# UCC28070_Control.net
KiCad netlist of a schematic drawn in Altium Designer
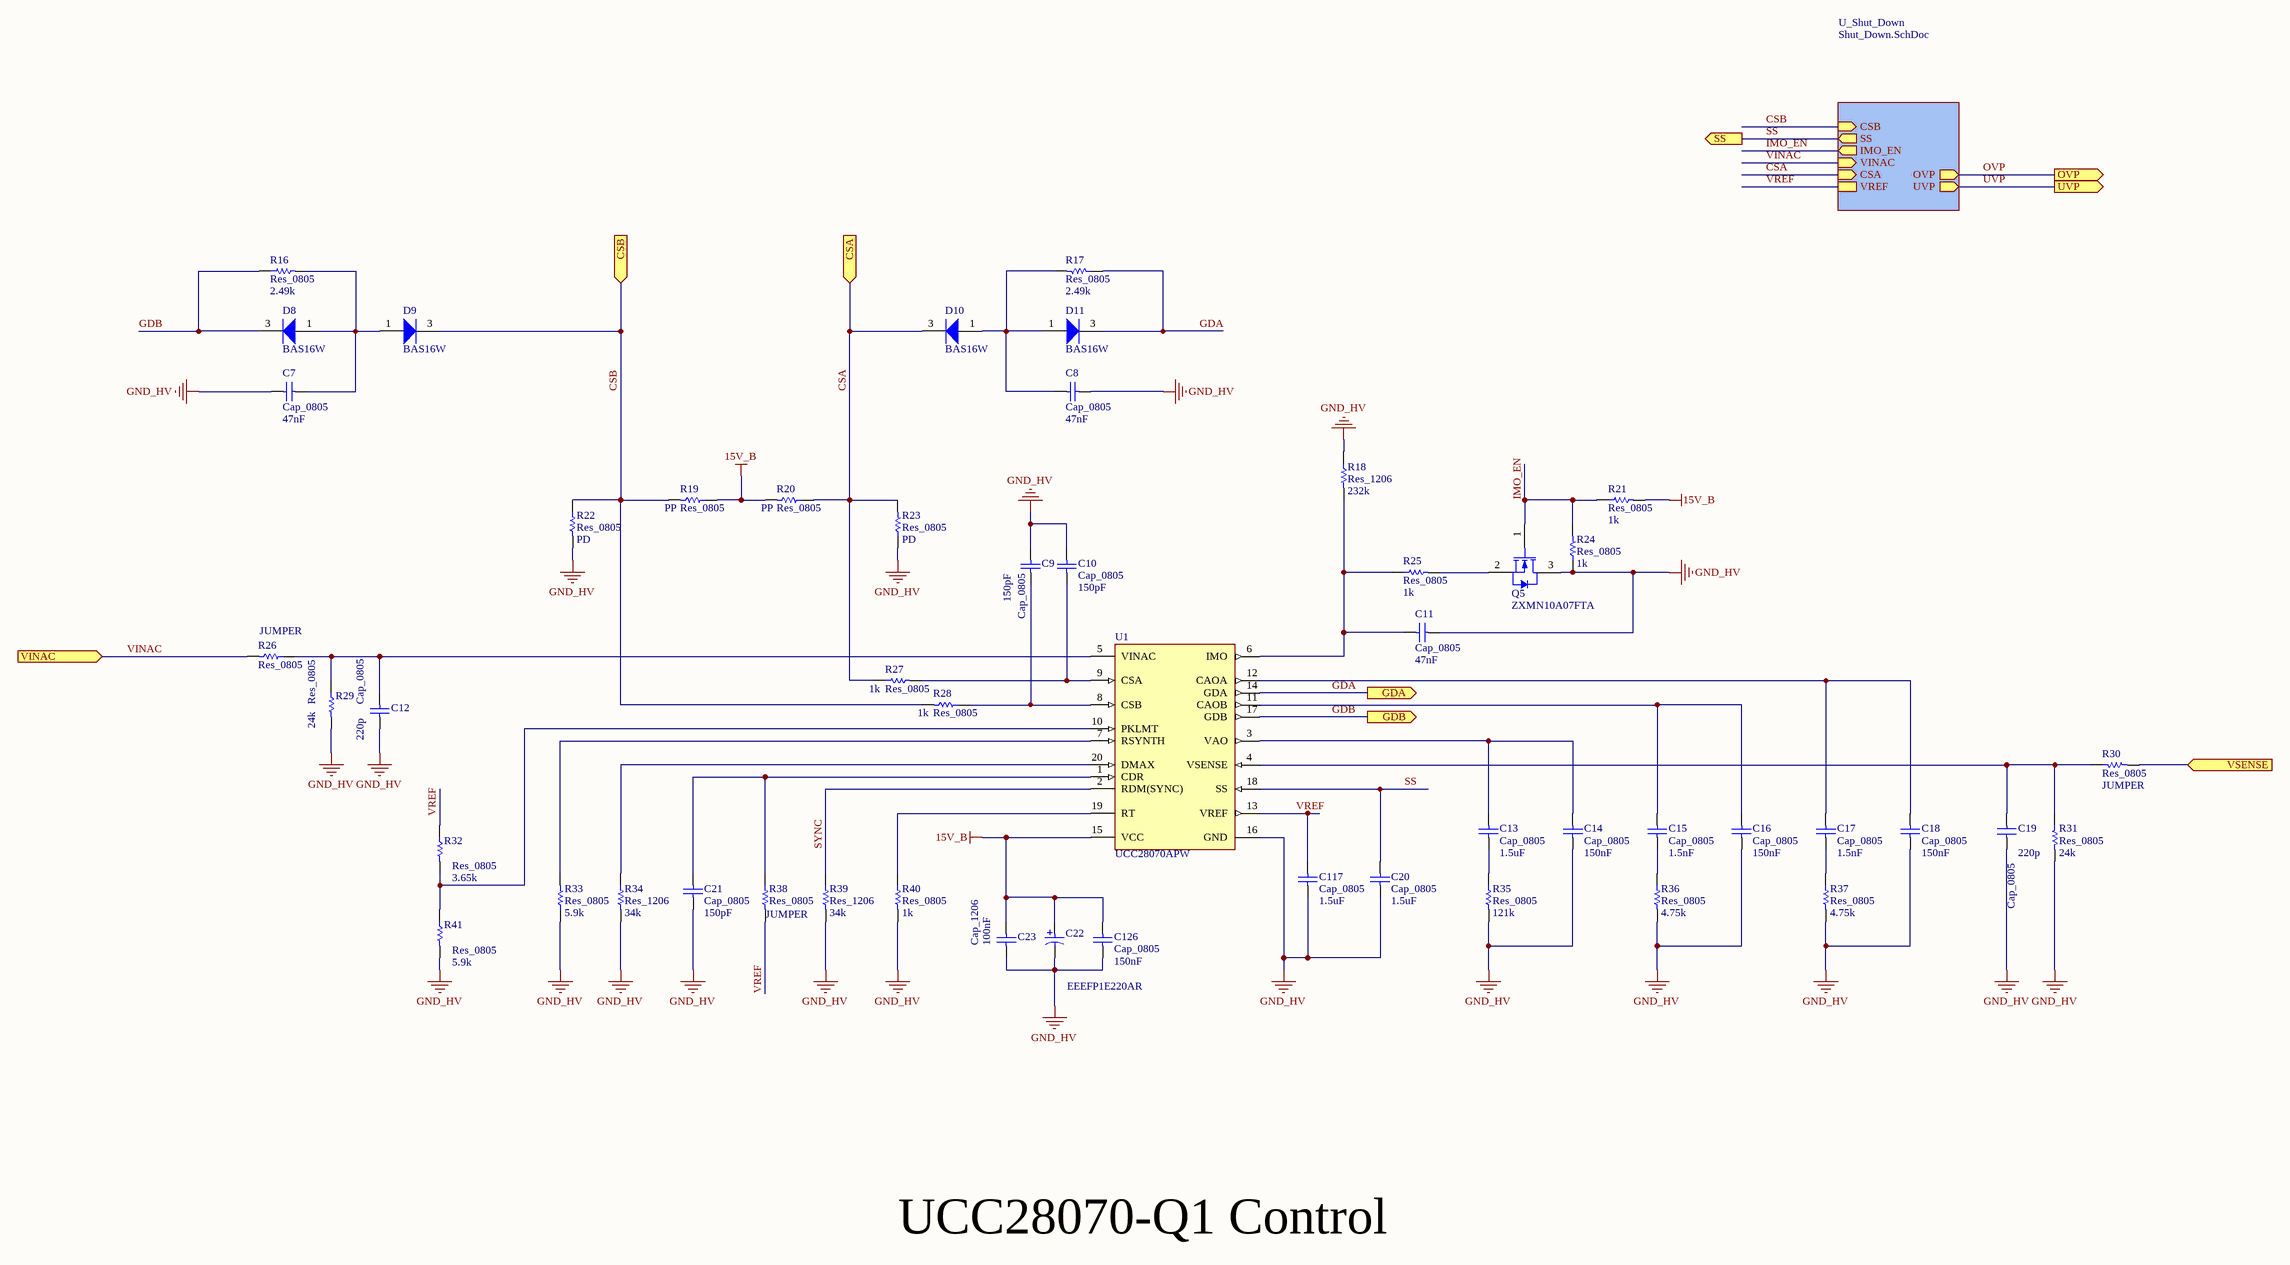
[diagram p0: UCC28070_Control.SchDoc]

(export (version "E")
  (design (tool "Eeschema 10.0.6"))
  (components
    (comp (ref "C7")
      (value "Cap_0805")
      (footprint "SMD-0805C")
      (description "Capacitor")
      (fields (field (name "SIZE") "47nF") (field (name "PUBLISHER") "Altium Limited"))
      (libsource (lib "Miscellaneous Devices") (part "Cap"))
    )
    (comp (ref "C8")
      (value "Cap_0805")
      (footprint "SMD-0805C")
      (description "Capacitor")
      (fields (field (name "SIZE") "47nF") (field (name "PUBLISHER") "Altium Limited"))
      (libsource (lib "Miscellaneous Devices") (part "Cap"))
    )
    (comp (ref "C9")
      (value "Cap_0805")
      (footprint "SMD-0805C")
      (description "Capacitor")
      (fields (field (name "SIZE") "150pF") (field (name "PUBLISHER") "Altium Limited"))
      (libsource (lib "Miscellaneous Devices") (part "Cap"))
    )
    (comp (ref "C10")
      (value "Cap_0805")
      (footprint "SMD-0805C")
      (description "Capacitor")
      (fields (field (name "SIZE") "150pF") (field (name "PUBLISHER") "Altium Limited"))
      (libsource (lib "Miscellaneous Devices") (part "Cap"))
    )
    (comp (ref "C11")
      (value "Cap_0805")
      (footprint "SMD-0805C")
      (description "Capacitor")
      (fields (field (name "SIZE") "47nF") (field (name "PUBLISHER") "Altium Limited"))
      (libsource (lib "Miscellaneous Devices") (part "Cap"))
    )
    (comp (ref "C12")
      (value "Cap_0805")
      (footprint "SMD-0805C")
      (description "Capacitor")
      (fields (field (name "SIZE") "220p") (field (name "PUBLISHER") "Altium Limited"))
      (libsource (lib "Miscellaneous Devices") (part "Cap"))
    )
    (comp (ref "C13")
      (value "Cap_0805")
      (footprint "SMD-0805C")
      (description "Capacitor")
      (fields (field (name "SIZE") "1.5uF") (field (name "PUBLISHER") "Altium Limited"))
      (libsource (lib "Miscellaneous Devices") (part "Cap"))
    )
    (comp (ref "C14")
      (value "Cap_0805")
      (footprint "SMD-0805C")
      (description "Capacitor")
      (fields (field (name "SIZE") "150nF") (field (name "PUBLISHER") "Altium Limited"))
      (libsource (lib "Miscellaneous Devices") (part "Cap"))
    )
    (comp (ref "C15")
      (value "Cap_0805")
      (footprint "SMD-0805C")
      (description "Capacitor")
      (fields (field (name "SIZE") "1.5nF") (field (name "PUBLISHER") "Altium Limited"))
      (libsource (lib "Miscellaneous Devices") (part "Cap"))
    )
    (comp (ref "C16")
      (value "Cap_0805")
      (footprint "SMD-0805C")
      (description "Capacitor")
      (fields (field (name "SIZE") "150nF") (field (name "PUBLISHER") "Altium Limited"))
      (libsource (lib "Miscellaneous Devices") (part "Cap"))
    )
    (comp (ref "C17")
      (value "Cap_0805")
      (footprint "SMD-0805C")
      (description "Capacitor")
      (fields (field (name "SIZE") "1.5nF") (field (name "PUBLISHER") "Altium Limited"))
      (libsource (lib "Miscellaneous Devices") (part "Cap"))
    )
    (comp (ref "C18")
      (value "Cap_0805")
      (footprint "SMD-0805C")
      (description "Capacitor")
      (fields (field (name "SIZE") "150nF") (field (name "PUBLISHER") "Altium Limited"))
      (libsource (lib "Miscellaneous Devices") (part "Cap"))
    )
    (comp (ref "C19")
      (value "Cap_0805")
      (footprint "SMD-0805C")
      (description "Capacitor")
      (fields (field (name "SIZE") "220p") (field (name "PUBLISHER") "Altium Limited"))
      (libsource (lib "Miscellaneous Devices") (part "Cap"))
    )
    (comp (ref "C20")
      (value "Cap_0805")
      (footprint "SMD-0805C")
      (description "Capacitor")
      (fields (field (name "SIZE") "1.5uF") (field (name "PUBLISHER") "Altium Limited"))
      (libsource (lib "Miscellaneous Devices") (part "Cap"))
    )
    (comp (ref "C21")
      (value "Cap_0805")
      (footprint "SMD-0805C")
      (description "Capacitor")
      (fields (field (name "SIZE") "150pF") (field (name "PUBLISHER") "Altium Limited"))
      (libsource (lib "Miscellaneous Devices") (part "Cap"))
    )
    (comp (ref "C22")
      (value "EEEFP1E220AR")
      (footprint "PNSC-FP-V-C_V")
      (fields (field (name "MANUFACTURER") "Panasonic"))
      (libsource (lib "Altium Content Vault") (part "CAP-P-2"))
    )
    (comp (ref "C23")
      (value "Cap_1206")
      (footprint "SMD-1206C")
      (description "Capacitor")
      (fields (field (name "ALTIUM_VALUE") "100nF") (field (name "PUBLISHER") "Altium Limited"))
      (libsource (lib "Miscellaneous Devices") (part "Cap"))
    )
    (comp (ref "C117")
      (value "Cap_0805")
      (footprint "SMD-0805C")
      (description "Capacitor")
      (fields (field (name "SIZE") "1.5uF") (field (name "PUBLISHER") "Altium Limited"))
      (libsource (lib "Miscellaneous Devices") (part "Cap"))
    )
    (comp (ref "C126")
      (value "Cap_0805")
      (footprint "SMD-0805C")
      (description "Capacitor")
      (fields (field (name "SIZE") "150nF") (field (name "PUBLISHER") "Altium Limited"))
      (libsource (lib "Miscellaneous Devices") (part "Cap"))
    )
    (comp (ref "D8")
      (value "BAS16W")
      (footprint "SOT95P278X110-3N")
      (description "Silicon Switching Diode, SOT323, Reel, Green")
      (fields (field (name "MANUFACTURER") "Infineon"))
      (libsource (lib "PFC_Stage") (part "BAS16"))
    )
    (comp (ref "D9")
      (value "BAS16W")
      (footprint "SOT95P278X110-3N")
      (description "Silicon Switching Diode, SOT323, Reel, Green")
      (fields (field (name "MANUFACTURER") "Infineon"))
      (libsource (lib "PFC_Stage") (part "BAS16"))
    )
    (comp (ref "D10")
      (value "BAS16W")
      (footprint "SOT95P278X110-3N")
      (description "Silicon Switching Diode, SOT323, Reel, Green")
      (fields (field (name "MANUFACTURER") "Infineon"))
      (libsource (lib "PFC_Stage") (part "BAS16"))
    )
    (comp (ref "D11")
      (value "BAS16W")
      (footprint "SOT95P278X110-3N")
      (description "Silicon Switching Diode, SOT323, Reel, Green")
      (fields (field (name "MANUFACTURER") "Infineon"))
      (libsource (lib "PFC_Stage") (part "BAS16"))
    )
    (comp (ref "Q5")
      (value "ZXMN10A07FTA")
      (footprint "DIOD-SOT23-3_D_V")
      (description "N-Channel Enhancement Mode MOSFET, 100 V, -55 to 150 degC, 3-Pin SOT23, RoHS, Tape and Reel")
      (fields (field (name "MANUFACTURER") "Diodes Inc"))
      (libsource (lib "Altium Content Vault") (part "NEMOS-GSD-3"))
    )
    (comp (ref "R16")
      (value "Res_0805")
      (footprint "WRIS-KSKE_0805_H=0.6mm")
      (description "Resistor")
      (fields (field (name "ALTIUM_VALUE") "2.49k") (field (name "PUBLISHER") "Altium Limited"))
      (libsource (lib "Miscellaneous Devices") (part "Res1"))
    )
    (comp (ref "R17")
      (value "Res_0805")
      (footprint "WRIS-KSKE_0805_H=0.6mm")
      (description "Resistor")
      (fields (field (name "ALTIUM_VALUE") "2.49k") (field (name "PUBLISHER") "Altium Limited"))
      (libsource (lib "Miscellaneous Devices") (part "Res1"))
    )
    (comp (ref "R18")
      (value "Res_1206")
      (footprint "WRIS-KSKE_1206_H=0.6mm")
      (description "Resistor")
      (fields (field (name "ALTIUM_VALUE") "232k") (field (name "PUBLISHER") "Altium Limited"))
      (libsource (lib "Miscellaneous Devices") (part "Res1"))
    )
    (comp (ref "R19")
      (value "Res_0805")
      (footprint "WRIS-KSKE_0805_H=0.6mm")
      (description "Resistor")
      (fields (field (name "ALTIUM_VALUE") "PP") (field (name "PUBLISHER") "Altium Limited"))
      (libsource (lib "Miscellaneous Devices") (part "Res1"))
    )
    (comp (ref "R20")
      (value "Res_0805")
      (footprint "WRIS-KSKE_0805_H=0.6mm")
      (description "Resistor")
      (fields (field (name "ALTIUM_VALUE") "PP") (field (name "PUBLISHER") "Altium Limited"))
      (libsource (lib "Miscellaneous Devices") (part "Res1"))
    )
    (comp (ref "R21")
      (value "Res_0805")
      (footprint "WRIS-KSKE_0805_H=0.6mm")
      (description "Resistor")
      (fields (field (name "ALTIUM_VALUE") "1k") (field (name "PUBLISHER") "Altium Limited"))
      (libsource (lib "Miscellaneous Devices") (part "Res1"))
    )
    (comp (ref "R22")
      (value "Res_0805")
      (footprint "WRIS-KSKE_0805_H=0.6mm")
      (description "Resistor")
      (fields (field (name "ALTIUM_VALUE") "PD") (field (name "PUBLISHER") "Altium Limited"))
      (libsource (lib "Miscellaneous Devices") (part "Res1"))
    )
    (comp (ref "R23")
      (value "Res_0805")
      (footprint "WRIS-KSKE_0805_H=0.6mm")
      (description "Resistor")
      (fields (field (name "ALTIUM_VALUE") "PD") (field (name "PUBLISHER") "Altium Limited"))
      (libsource (lib "Miscellaneous Devices") (part "Res1"))
    )
    (comp (ref "R24")
      (value "Res_0805")
      (footprint "WRIS-KSKE_0805_H=0.6mm")
      (description "Resistor")
      (fields (field (name "ALTIUM_VALUE") "1k") (field (name "PUBLISHER") "Altium Limited"))
      (libsource (lib "Miscellaneous Devices") (part "Res1"))
    )
    (comp (ref "R25")
      (value "Res_0805")
      (footprint "WRIS-KSKE_0805_H=0.6mm")
      (description "Resistor")
      (fields (field (name "ALTIUM_VALUE") "1k") (field (name "PUBLISHER") "Altium Limited"))
      (libsource (lib "Miscellaneous Devices") (part "Res1"))
    )
    (comp (ref "R26")
      (value "Res_0805")
      (footprint "WRIS-KSKE_0805_H=0.6mm")
      (description "Resistor")
      (fields (field (name "ALTIUM_VALUE") "JUMPER") (field (name "PUBLISHER") "Altium Limited"))
      (libsource (lib "Miscellaneous Devices") (part "Res1"))
    )
    (comp (ref "R27")
      (value "Res_0805")
      (footprint "WRIS-KSKE_0805_H=0.6mm")
      (description "Resistor")
      (fields (field (name "ALTIUM_VALUE") "1k") (field (name "PUBLISHER") "Altium Limited"))
      (libsource (lib "Miscellaneous Devices") (part "Res1"))
    )
    (comp (ref "R28")
      (value "Res_0805")
      (footprint "WRIS-KSKE_0805_H=0.6mm")
      (description "Resistor")
      (fields (field (name "ALTIUM_VALUE") "1k") (field (name "PUBLISHER") "Altium Limited"))
      (libsource (lib "Miscellaneous Devices") (part "Res1"))
    )
    (comp (ref "R29")
      (value "Res_0805")
      (footprint "WRIS-KSKE_0805_H=0.6mm")
      (description "Resistor")
      (fields (field (name "ALTIUM_VALUE") "24k") (field (name "PUBLISHER") "Altium Limited"))
      (libsource (lib "Miscellaneous Devices") (part "Res1"))
    )
    (comp (ref "R30")
      (value "Res_0805")
      (footprint "WRIS-KSKE_0805_H=0.6mm")
      (description "Resistor")
      (fields (field (name "ALTIUM_VALUE") "JUMPER") (field (name "PUBLISHER") "Altium Limited"))
      (libsource (lib "Miscellaneous Devices") (part "Res1"))
    )
    (comp (ref "R31")
      (value "Res_0805")
      (footprint "WRIS-KSKE_0805_H=0.6mm")
      (description "Resistor")
      (fields (field (name "ALTIUM_VALUE") "24k") (field (name "PUBLISHER") "Altium Limited"))
      (libsource (lib "Miscellaneous Devices") (part "Res1"))
    )
    (comp (ref "R32")
      (value "Res_0805")
      (footprint "WRIS-KSKE_0805_H=0.6mm")
      (description "Resistor")
      (fields (field (name "ALTIUM_VALUE") "3.65k") (field (name "PUBLISHER") "Altium Limited"))
      (libsource (lib "Miscellaneous Devices") (part "Res1"))
    )
    (comp (ref "R33")
      (value "Res_0805")
      (footprint "WRIS-KSKE_0805_H=0.6mm")
      (description "Resistor")
      (fields (field (name "ALTIUM_VALUE") "5.9k") (field (name "PUBLISHER") "Altium Limited"))
      (libsource (lib "Miscellaneous Devices") (part "Res1"))
    )
    (comp (ref "R34")
      (value "Res_1206")
      (footprint "WRIS-KSKE_1206_H=0.6mm")
      (description "Resistor")
      (fields (field (name "ALTIUM_VALUE") "34k") (field (name "PUBLISHER") "Altium Limited"))
      (libsource (lib "Miscellaneous Devices") (part "Res1"))
    )
    (comp (ref "R35")
      (value "Res_0805")
      (footprint "WRIS-KSKE_0805_H=0.6mm")
      (description "Resistor")
      (fields (field (name "ALTIUM_VALUE") "121k") (field (name "PUBLISHER") "Altium Limited"))
      (libsource (lib "Miscellaneous Devices") (part "Res1"))
    )
    (comp (ref "R36")
      (value "Res_0805")
      (footprint "WRIS-KSKE_0805_H=0.6mm")
      (description "Resistor")
      (fields (field (name "ALTIUM_VALUE") "4.75k") (field (name "PUBLISHER") "Altium Limited"))
      (libsource (lib "Miscellaneous Devices") (part "Res1"))
    )
    (comp (ref "R37")
      (value "Res_0805")
      (footprint "WRIS-KSKE_0805_H=0.6mm")
      (description "Resistor")
      (fields (field (name "ALTIUM_VALUE") "4.75k") (field (name "PUBLISHER") "Altium Limited"))
      (libsource (lib "Miscellaneous Devices") (part "Res1"))
    )
    (comp (ref "R38")
      (value "Res_0805")
      (footprint "WRIS-KSKE_0805_H=0.6mm")
      (description "Resistor")
      (fields (field (name "ALTIUM_VALUE") "JUMPER") (field (name "PUBLISHER") "Altium Limited"))
      (libsource (lib "Miscellaneous Devices") (part "Res1"))
    )
    (comp (ref "R39")
      (value "Res_1206")
      (footprint "WRIS-KSKE_1206_H=0.6mm")
      (description "Resistor")
      (fields (field (name "ALTIUM_VALUE") "34k") (field (name "PUBLISHER") "Altium Limited"))
      (libsource (lib "Miscellaneous Devices") (part "Res1"))
    )
    (comp (ref "R40")
      (value "Res_0805")
      (footprint "WRIS-KSKE_0805_H=0.6mm")
      (description "Resistor")
      (fields (field (name "ALTIUM_VALUE") "1k") (field (name "PUBLISHER") "Altium Limited"))
      (libsource (lib "Miscellaneous Devices") (part "Res1"))
    )
    (comp (ref "R41")
      (value "Res_0805")
      (footprint "WRIS-KSKE_0805_H=0.6mm")
      (description "Resistor")
      (fields (field (name "ALTIUM_VALUE") "5.9k") (field (name "PUBLISHER") "Altium Limited"))
      (libsource (lib "Miscellaneous Devices") (part "Res1"))
    )
    (comp (ref "U1")
      (value "UCC28070APW")
      (footprint "TSOP65P640X120_HS-21N")
      (fields (field (name "MANUFACTURER") "Texas Instruments"))
      (libsource (lib "PFC_Stage") (part "CMP-0333-00336-2"))
    )
  )
  (nets
    (net (code "1") (name "/CSA") (class "Default")
      (node (ref "D10") (pin "3") (pinfunction "K_3") (pintype "passive"))
      (node (ref "R20") (pin "1") (pinfunction "1_1") (pintype "passive"))
      (node (ref "R23") (pin "2") (pinfunction "2_2") (pintype "passive"))
      (node (ref "R27") (pin "1") (pinfunction "1_1") (pintype "passive"))
    )
    (net (code "2") (name "/CSB") (class "Default")
      (node (ref "D9") (pin "3") (pinfunction "K_3") (pintype "passive"))
      (node (ref "R19") (pin "2") (pinfunction "2_2") (pintype "passive"))
      (node (ref "R22") (pin "1") (pinfunction "1_1") (pintype "passive"))
      (node (ref "R28") (pin "2") (pinfunction "2_2") (pintype "passive"))
    )
    (net (code "3") (name "/GDA") (class "Default")
      (node (ref "D11") (pin "3") (pinfunction "K_3") (pintype "passive"))
      (node (ref "R17") (pin "1") (pinfunction "1_1") (pintype "passive"))
      (node (ref "U1") (pin "14") (pinfunction "GDA_14") (pintype "output"))
    )
    (net (code "4") (name "/GDB") (class "Default")
      (node (ref "D8") (pin "3") (pinfunction "K_3") (pintype "passive"))
      (node (ref "R16") (pin "1") (pinfunction "1_1") (pintype "passive"))
      (node (ref "U1") (pin "17") (pinfunction "GDB_17") (pintype "output"))
    )
    (net (code "5") (name "/IMO_EN") (class "Default")
      (node (ref "Q5") (pin "1") (pinfunction "G_1") (pintype "passive"))
      (node (ref "R21") (pin "1") (pinfunction "1_1") (pintype "passive"))
      (node (ref "R24") (pin "2") (pinfunction "2_2") (pintype "passive"))
    )
    (net (code "7") (name "/SS") (class "Default")
      (node (ref "C20") (pin "1") (pinfunction "1_1") (pintype "passive"))
      (node (ref "U1") (pin "18") (pinfunction "SS_18") (pintype "input"))
    )
    (net (code "8") (name "/SYNC") (class "Default")
      (node (ref "R39") (pin "1") (pinfunction "1_1") (pintype "passive"))
      (node (ref "U1") (pin "2") (pinfunction "RDM(SYNC)_2") (pintype "passive"))
    )
    (net (code "10") (name "/VINAC") (class "Default")
      (node (ref "R26") (pin "2") (pinfunction "2_2") (pintype "passive"))
    )
    (net (code "11") (name "/VREF") (class "Default")
      (node (ref "C117") (pin "1") (pinfunction "1_1") (pintype "passive"))
      (node (ref "R32") (pin "1") (pinfunction "1_1") (pintype "passive"))
      (node (ref "R38") (pin "2") (pinfunction "2_2") (pintype "passive"))
      (node (ref "U1") (pin "13") (pinfunction "VREF_13") (pintype "output"))
    )
    (net (code "12") (name "/VSENSE") (class "Default")
      (node (ref "R30") (pin "2") (pinfunction "2_2") (pintype "passive"))
    )
    (net (code "13") (name "15V_B") (class "Default")
      (node (ref "C126") (pin "1") (pinfunction "1_1") (pintype "passive"))
      (node (ref "C22") (pin "1") (pinfunction "1_1") (pintype "passive"))
      (node (ref "C23") (pin "1") (pinfunction "1_1") (pintype "passive"))
      (node (ref "R19") (pin "1") (pinfunction "1_1") (pintype "passive"))
      (node (ref "R20") (pin "2") (pinfunction "2_2") (pintype "passive"))
      (node (ref "R21") (pin "2") (pinfunction "2_2") (pintype "passive"))
      (node (ref "U1") (pin "15") (pinfunction "VCC_15") (pintype "power_in"))
    )
    (net (code "14") (name "GND_HV") (class "Default")
      (node (ref "C10") (pin "1") (pinfunction "1_1") (pintype "passive"))
      (node (ref "C11") (pin "2") (pinfunction "2_2") (pintype "passive"))
      (node (ref "C117") (pin "2") (pinfunction "2_2") (pintype "passive"))
      (node (ref "C12") (pin "2") (pinfunction "2_2") (pintype "passive"))
      (node (ref "C126") (pin "2") (pinfunction "2_2") (pintype "passive"))
      (node (ref "C14") (pin "2") (pinfunction "2_2") (pintype "passive"))
      (node (ref "C16") (pin "2") (pinfunction "2_2") (pintype "passive"))
      (node (ref "C18") (pin "2") (pinfunction "2_2") (pintype "passive"))
      (node (ref "C19") (pin "2") (pinfunction "2_2") (pintype "passive"))
      (node (ref "C20") (pin "2") (pinfunction "2_2") (pintype "passive"))
      (node (ref "C21") (pin "2") (pinfunction "2_2") (pintype "passive"))
      (node (ref "C22") (pin "2") (pinfunction "2_2") (pintype "passive"))
      (node (ref "C23") (pin "2") (pinfunction "2_2") (pintype "passive"))
      (node (ref "C7") (pin "1") (pinfunction "1_1") (pintype "passive"))
      (node (ref "C8") (pin "1") (pinfunction "1_1") (pintype "passive"))
      (node (ref "C9") (pin "1") (pinfunction "1_1") (pintype "passive"))
      (node (ref "Q5") (pin "3") (pinfunction "D_3") (pintype "passive"))
      (node (ref "R18") (pin "1") (pinfunction "1_1") (pintype "passive"))
      (node (ref "R22") (pin "2") (pinfunction "2_2") (pintype "passive"))
      (node (ref "R23") (pin "1") (pinfunction "1_1") (pintype "passive"))
      (node (ref "R24") (pin "1") (pinfunction "1_1") (pintype "passive"))
      (node (ref "R29") (pin "2") (pinfunction "2_2") (pintype "passive"))
      (node (ref "R31") (pin "2") (pinfunction "2_2") (pintype "passive"))
      (node (ref "R33") (pin "1") (pinfunction "1_1") (pintype "passive"))
      (node (ref "R34") (pin "2") (pinfunction "2_2") (pintype "passive"))
      (node (ref "R35") (pin "2") (pinfunction "2_2") (pintype "passive"))
      (node (ref "R36") (pin "2") (pinfunction "2_2") (pintype "passive"))
      (node (ref "R37") (pin "2") (pinfunction "2_2") (pintype "passive"))
      (node (ref "R39") (pin "2") (pinfunction "2_2") (pintype "passive"))
      (node (ref "R40") (pin "2") (pinfunction "2_2") (pintype "passive"))
      (node (ref "R41") (pin "2") (pinfunction "2_2") (pintype "passive"))
      (node (ref "U1") (pin "16") (pinfunction "GND_16") (pintype "power_in"))
    )
    (net (code "15") (name "Net-(C13-Pad2)") (class "Default")
      (node (ref "C13") (pin "2") (pinfunction "2_2") (pintype "passive"))
      (node (ref "R35") (pin "1") (pinfunction "1_1") (pintype "passive"))
    )
    (net (code "16") (name "Net-(C15-Pad2)") (class "Default")
      (node (ref "C15") (pin "2") (pinfunction "2_2") (pintype "passive"))
      (node (ref "R36") (pin "1") (pinfunction "1_1") (pintype "passive"))
    )
    (net (code "17") (name "Net-(C17-Pad2)") (class "Default")
      (node (ref "C17") (pin "2") (pinfunction "2_2") (pintype "passive"))
      (node (ref "R37") (pin "1") (pinfunction "1_1") (pintype "passive"))
    )
    (net (code "18") (name "Net-(D8-A)") (class "Default")
      (node (ref "C7") (pin "2") (pinfunction "2_2") (pintype "passive"))
      (node (ref "D8") (pin "1") (pinfunction "A_1") (pintype "passive"))
      (node (ref "D9") (pin "1") (pinfunction "A_1") (pintype "passive"))
      (node (ref "R16") (pin "2") (pinfunction "2_2") (pintype "passive"))
    )
    (net (code "19") (name "Net-(D10-A)") (class "Default")
      (node (ref "C8") (pin "2") (pinfunction "2_2") (pintype "passive"))
      (node (ref "D10") (pin "1") (pinfunction "A_1") (pintype "passive"))
      (node (ref "D11") (pin "1") (pinfunction "A_1") (pintype "passive"))
      (node (ref "R17") (pin "2") (pinfunction "2_2") (pintype "passive"))
    )
    (net (code "20") (name "Net-(Q5-S)") (class "Default")
      (node (ref "Q5") (pin "2") (pinfunction "S_2") (pintype "passive"))
      (node (ref "R25") (pin "2") (pinfunction "2_2") (pintype "passive"))
    )
    (net (code "21") (name "Net-(U1-CAOA)") (class "Default")
      (node (ref "C17") (pin "1") (pinfunction "1_1") (pintype "passive"))
      (node (ref "C18") (pin "1") (pinfunction "1_1") (pintype "passive"))
      (node (ref "U1") (pin "12") (pinfunction "CAOA_12") (pintype "output"))
    )
    (net (code "22") (name "Net-(U1-CAOB)") (class "Default")
      (node (ref "C15") (pin "1") (pinfunction "1_1") (pintype "passive"))
      (node (ref "C16") (pin "1") (pinfunction "1_1") (pintype "passive"))
      (node (ref "U1") (pin "11") (pinfunction "CAOB_11") (pintype "output"))
    )
    (net (code "23") (name "Net-(U1-CDR)") (class "Default")
      (node (ref "C21") (pin "1") (pinfunction "1_1") (pintype "passive"))
      (node (ref "R38") (pin "1") (pinfunction "1_1") (pintype "passive"))
      (node (ref "U1") (pin "1") (pinfunction "CDR_1") (pintype "input"))
    )
    (net (code "24") (name "Net-(U1-CSA)") (class "Default")
      (node (ref "C10") (pin "2") (pinfunction "2_2") (pintype "passive"))
      (node (ref "R27") (pin "2") (pinfunction "2_2") (pintype "passive"))
      (node (ref "U1") (pin "9") (pinfunction "CSA_9") (pintype "input"))
    )
    (net (code "25") (name "Net-(U1-CSB)") (class "Default")
      (node (ref "C9") (pin "2") (pinfunction "2_2") (pintype "passive"))
      (node (ref "R28") (pin "1") (pinfunction "1_1") (pintype "passive"))
      (node (ref "U1") (pin "8") (pinfunction "CSB_8") (pintype "input"))
    )
    (net (code "26") (name "Net-(U1-DMAX)") (class "Default")
      (node (ref "R34") (pin "1") (pinfunction "1_1") (pintype "passive"))
      (node (ref "U1") (pin "20") (pinfunction "DMAX_20") (pintype "input"))
    )
    (net (code "27") (name "Net-(U1-IMO)") (class "Default")
      (node (ref "C11") (pin "1") (pinfunction "1_1") (pintype "passive"))
      (node (ref "R18") (pin "2") (pinfunction "2_2") (pintype "passive"))
      (node (ref "R25") (pin "1") (pinfunction "1_1") (pintype "passive"))
      (node (ref "U1") (pin "6") (pinfunction "IMO_6") (pintype "output"))
    )
    (net (code "28") (name "Net-(U1-PKLMT)") (class "Default")
      (node (ref "R32") (pin "2") (pinfunction "2_2") (pintype "passive"))
      (node (ref "R41") (pin "1") (pinfunction "1_1") (pintype "passive"))
      (node (ref "U1") (pin "10") (pinfunction "PKLMT_10") (pintype "input"))
    )
    (net (code "29") (name "Net-(U1-RSYNTH)") (class "Default")
      (node (ref "R33") (pin "2") (pinfunction "2_2") (pintype "passive"))
      (node (ref "U1") (pin "7") (pinfunction "RSYNTH_7") (pintype "input"))
    )
    (net (code "30") (name "Net-(U1-RT)") (class "Default")
      (node (ref "R40") (pin "1") (pinfunction "1_1") (pintype "passive"))
      (node (ref "U1") (pin "19") (pinfunction "RT_19") (pintype "passive"))
    )
    (net (code "31") (name "Net-(U1-VAO)") (class "Default")
      (node (ref "C13") (pin "1") (pinfunction "1_1") (pintype "passive"))
      (node (ref "C14") (pin "1") (pinfunction "1_1") (pintype "passive"))
      (node (ref "U1") (pin "3") (pinfunction "VAO_3") (pintype "output"))
    )
    (net (code "32") (name "Net-(U1-VINAC)") (class "Default")
      (node (ref "C12") (pin "1") (pinfunction "1_1") (pintype "passive"))
      (node (ref "R26") (pin "1") (pinfunction "1_1") (pintype "passive"))
      (node (ref "R29") (pin "1") (pinfunction "1_1") (pintype "passive"))
      (node (ref "U1") (pin "5") (pinfunction "VINAC_5") (pintype "power_in"))
    )
    (net (code "33") (name "Net-(U1-VSENSE)") (class "Default")
      (node (ref "C19") (pin "1") (pinfunction "1_1") (pintype "passive"))
      (node (ref "R30") (pin "1") (pinfunction "1_1") (pintype "passive"))
      (node (ref "R31") (pin "1") (pinfunction "1_1") (pintype "passive"))
      (node (ref "U1") (pin "4") (pinfunction "VSENSE_4") (pintype "input"))
    )
  )
)
